# inverter-supply-lv.net
KiCad netlist of a schematic drawn in EAGLE
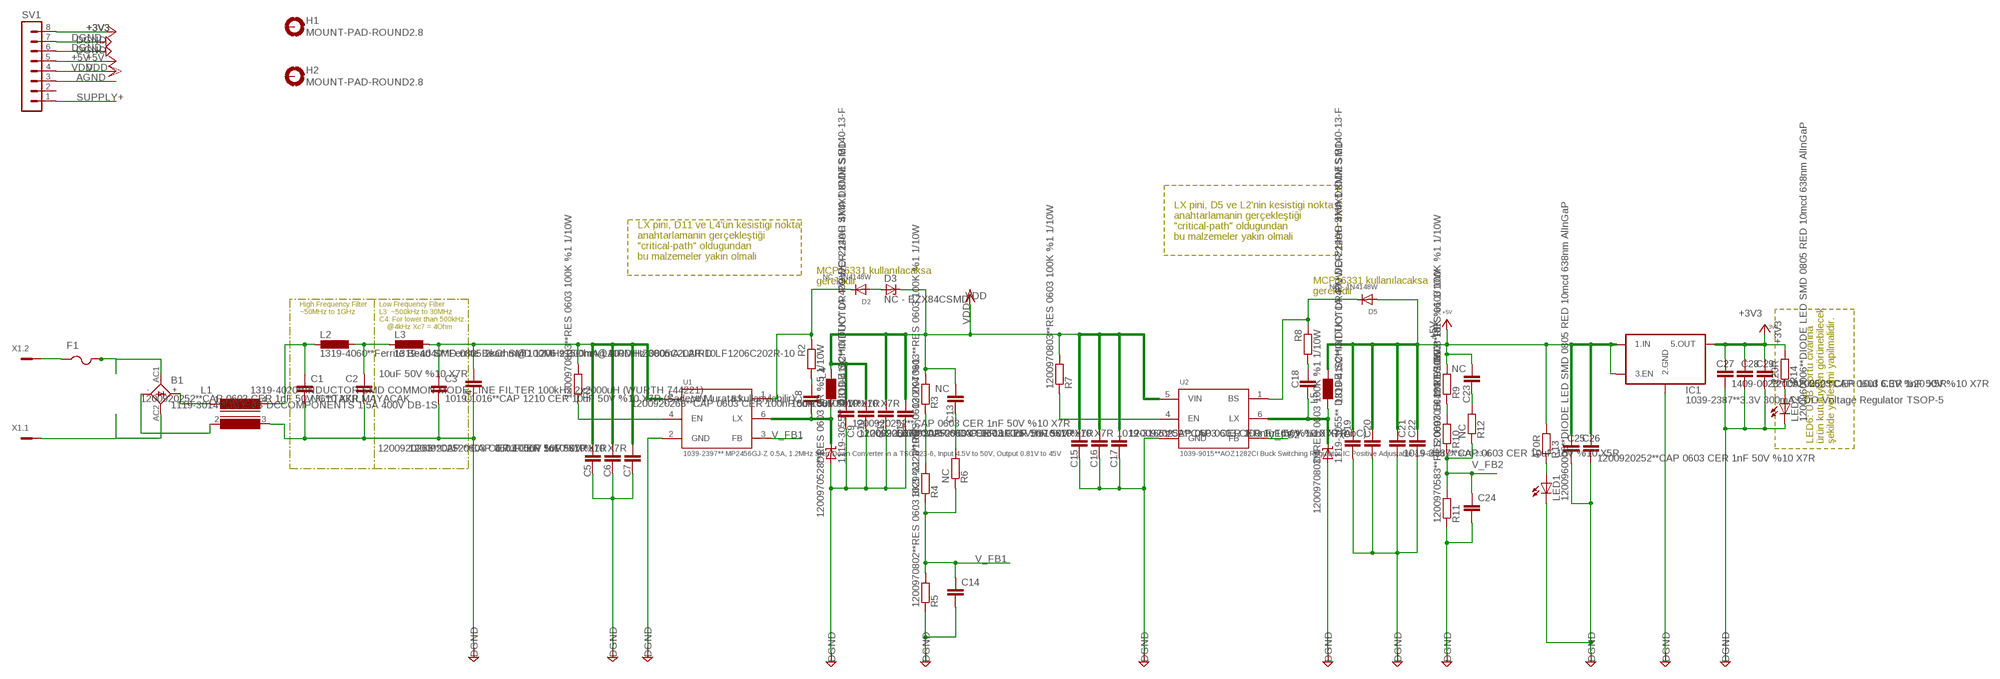
[diagram p0: schematic, sheet 1]

(export (version "E")
  (design (tool "Eeschema 10.0.6"))
  (components
    (comp (ref "B1")
      (value "1119-3014**DB154S DCCOMPONENTS 1.5A 400V DB-1S")
      (footprint "eagle-import:DF005S_DF10S")
      (libsource (lib "eagle-import") (part "DF005S_DF10S"))
    )
    (comp (ref "C1")
      (value "NC**TAKILMAYACAK")
      (footprint "eagle-import:C0603")
      (libsource (lib "eagle-import") (part "C-EUC0603"))
    )
    (comp (ref "C2")
      (value "1200920252**CAP 0603 CER 1nF 50V %10 X7R")
      (footprint "eagle-import:C0603_ENKO")
      (libsource (lib "eagle-import") (part "C-EUC0603E"))
    )
    (comp (ref "C3")
      (value "1019-1016**CAP 1210 CER 10uF 50V %10 X7R (Sadece Murata kullanylabilir)")
      (footprint "eagle-import:C1210")
      (libsource (lib "eagle-import") (part "C-EUC1210"))
    )
    (comp (ref "C4")
      (value "10uF 50V %10 X7R")
      (footprint "eagle-import:C0805_ENKO")
      (libsource (lib "eagle-import") (part "C-EUC0805E"))
    )
    (comp (ref "C5")
      (value "4.7uF 50V %10 X7R")
      (footprint "eagle-import:C0805_ENKO")
      (libsource (lib "eagle-import") (part "C-EUC0805E"))
    )
    (comp (ref "C6")
      (value "1200920268**CAP 0603 CER 100nF 50V %10 X7R")
      (footprint "eagle-import:C0603_ENKO")
      (libsource (lib "eagle-import") (part "C-EUC0603E"))
    )
    (comp (ref "C7")
      (value "1200920252**CAP 0603 CER 1nF 50V %10 X7R")
      (footprint "eagle-import:C0603_ENKO")
      (libsource (lib "eagle-import") (part "C-EUC0603E"))
    )
    (comp (ref "C8")
      (value "1200920268**CAP 0603 CER 100nF 50V %10 X7R")
      (footprint "eagle-import:C0603_ENKO")
      (libsource (lib "eagle-import") (part "C-EUC0603E"))
    )
    (comp (ref "C9")
      (value "1200920252**CAP 0603 CER 1nF 50V %10 X7R")
      (footprint "eagle-import:C0603_ENKO")
      (libsource (lib "eagle-import") (part "C-EUC0603E"))
    )
    (comp (ref "C10")
      (value "1200920268**CAP 0603 CER 100nF 50V %10 X7R")
      (footprint "eagle-import:C0603_ENKO")
      (libsource (lib "eagle-import") (part "C-EUC0603E"))
    )
    (comp (ref "C11")
      (value "10uF 50V %10 X7R")
      (footprint "eagle-import:C0805_ENKO")
      (libsource (lib "eagle-import") (part "C-EUC0805E"))
    )
    (comp (ref "C12")
      (value "10uF 50V %10 X7R")
      (footprint "eagle-import:C0805_ENKO")
      (libsource (lib "eagle-import") (part "C-EUC0805E"))
    )
    (comp (ref "C13")
      (value "NC")
      (footprint "eagle-import:C0603_ENKO")
      (libsource (lib "eagle-import") (part "C-EUC0603E"))
    )
    (comp (ref "C14")
      (value "1200920271**CAP 0603 CER 10pF 50V%10 COG")
      (footprint "eagle-import:C0603_ENKO")
      (libsource (lib "eagle-import") (part "C-EUC0603E"))
    )
    (comp (ref "C15")
      (value "1200920567**CAP 0603 CER 1uF 25V %10X7R")
      (footprint "eagle-import:C0603_ENKO")
      (libsource (lib "eagle-import") (part "C-EUC0603E"))
    )
    (comp (ref "C16")
      (value "1200920268**CAP 0603 CER 100nF 50V %10 X7R")
      (footprint "eagle-import:C0603_ENKO")
      (libsource (lib "eagle-import") (part "C-EUC0603E"))
    )
    (comp (ref "C17")
      (value "1200920252**CAP 0603 CER 1nF 50V %10 X7R")
      (footprint "eagle-import:C0603_ENKO")
      (libsource (lib "eagle-import") (part "C-EUC0603E"))
    )
    (comp (ref "C18")
      (value "1200920268**CAP 0603 CER 100nF 50V %10 X7R")
      (footprint "eagle-import:C0603_ENKO")
      (libsource (lib "eagle-import") (part "C-EUC0603E"))
    )
    (comp (ref "C19")
      (value "1200920252**CAP 0603 CER 1nF 50V %10 X7R")
      (footprint "eagle-import:C0603_ENKO")
      (libsource (lib "eagle-import") (part "C-EUC0603E"))
    )
    (comp (ref "C20")
      (value "1019-3166**CAP 0603 CER 100nF 16V %10 X7R (AbC)")
      (footprint "eagle-import:C0603_ENKO")
      (libsource (lib "eagle-import") (part "C-EUC0603E"))
    )
    (comp (ref "C21")
      (value "1019-3387**CAP 0603 CER 10uF 10V %10 X5R")
      (footprint "eagle-import:C0603_ENKO")
      (libsource (lib "eagle-import") (part "C-EUC0603E"))
    )
    (comp (ref "C22")
      (value "1019-3387**CAP 0603 CER 10uF 10V %10 X5R")
      (footprint "eagle-import:C0603_ENKO")
      (libsource (lib "eagle-import") (part "C-EUC0603E"))
    )
    (comp (ref "C23")
      (value "NC")
      (footprint "eagle-import:C0603_ENKO")
      (libsource (lib "eagle-import") (part "C-EUC0603E"))
    )
    (comp (ref "C24")
      (value "1200920271**CAP 0603 CER 10pF 50V%10 COG")
      (footprint "eagle-import:C0603_ENKO")
      (libsource (lib "eagle-import") (part "C-EUC0603E"))
    )
    (comp (ref "C25")
      (value "1019-3166**CAP 0603 CER 100nF 16V %10 X7R (AbC)")
      (footprint "eagle-import:C0603_ENKO")
      (libsource (lib "eagle-import") (part "C-EUC0603E"))
    )
    (comp (ref "C26")
      (value "1200920252**CAP 0603 CER 1nF 50V %10 X7R")
      (footprint "eagle-import:C0603_ENKO")
      (libsource (lib "eagle-import") (part "C-EUC0603E"))
    )
    (comp (ref "C27")
      (value "1409-0023**CAP 0603 CER 10uf 6.3V %20 X5R")
      (footprint "eagle-import:C0603_ENKO")
      (libsource (lib "eagle-import") (part "C-EUC0603E"))
    )
    (comp (ref "C28")
      (value "1019-3166**CAP 0603 CER 100nF 16V %10 X7R (AbC)")
      (footprint "eagle-import:C0603_ENKO")
      (libsource (lib "eagle-import") (part "C-EUC0603E"))
    )
    (comp (ref "C29")
      (value "1200920252**CAP 0603 CER 1nF 50V %10 X7R")
      (footprint "eagle-import:C0603_ENKO")
      (libsource (lib "eagle-import") (part "C-EUC0603E"))
    )
    (comp (ref "D1")
      (value "1119-3055** DIODE SCHOTTKY 1A 40V DO-214AC SMA DIODES B140-13-F")
      (footprint "eagle-import:SMA")
      (libsource (lib "eagle-import") (part "SD-SMA"))
    )
    (comp (ref "D2")
      (value "NC - 1N4148W")
      (footprint "eagle-import:SOD-123")
      (libsource (lib "eagle-import") (part "DIODESOD-123"))
    )
    (comp (ref "D3")
      (value "NC - BZX84CSMD")
      (footprint "eagle-import:TO236")
      (libsource (lib "eagle-import") (part "BZX84CSMD"))
    )
    (comp (ref "D4")
      (value "1119-3055** DIODE SCHOTTKY 1A 40V DO-214AC SMA DIODES B140-13-F")
      (footprint "eagle-import:SMA")
      (libsource (lib "eagle-import") (part "SD-SMA"))
    )
    (comp (ref "D5")
      (value "NC - 1N4148W")
      (footprint "eagle-import:SOD-123")
      (libsource (lib "eagle-import") (part "DIODESOD-123"))
    )
    (comp (ref "F1")
      (value "PTCFUSE-1206")
      (footprint "eagle-import:R1206")
      (libsource (lib "eagle-import") (part "PTCFUSE-1206"))
    )
    (comp (ref "H1")
      (value "MOUNT-PAD-ROUND2.8")
      (footprint "eagle-import:2,8-PAD")
      (libsource (lib "eagle-import") (part "MOUNT-PAD-ROUND2.8"))
    )
    (comp (ref "H2")
      (value "MOUNT-PAD-ROUND2.8")
      (footprint "eagle-import:2,8-PAD")
      (libsource (lib "eagle-import") (part "MOUNT-PAD-ROUND2.8"))
    )
    (comp (ref "IC1")
      (value "1039-2387**3.3V 300mA LDO Voltage Regulator TSOP-5")
      (footprint "eagle-import:NCP115ASN330T2G")
      (libsource (lib "eagle-import") (part "NCP115ASN330T2G"))
    )
    (comp (ref "L1")
      (value "1319-4020**INDUCTOR SMD COMMON MODE LINE FILTER 100kHz 2x2000uH (WURTH 744221)")
      (footprint "eagle-import:ARYA_COMMON_FILTER")
      (libsource (lib "eagle-import") (part "ARYA_COMMON_FILTER"))
    )
    (comp (ref "L2")
      (value "1319-4060**Ferrite Bead SMD 0805 2kOhm@100MHz 300mA LAIRD HZ0805C202R-10")
      (footprint "eagle-import:L2012C")
      (libsource (lib "eagle-import") (part "L-EUL2012C"))
    )
    (comp (ref "L3")
      (value "1319-4040**Ferrite Bead SMD 1206 915Ohm@100MHz 300mA LAIRD LF1206C202R-10")
      (footprint "eagle-import:L3216C")
      (libsource (lib "eagle-import") (part "L-EUL3216C"))
    )
    (comp (ref "L4")
      (value "1319-4102**INDUCTOR POWER 22UH 4X4X1.8MM SMD")
      (footprint "eagle-import:WE-PD2_S")
      (libsource (lib "eagle-import") (part "WE-PD2_S"))
    )
    (comp (ref "L5")
      (value "1319-4102**INDUCTOR POWER 22UH 4X4X1.8MM SMD")
      (footprint "eagle-import:WE-PD2_S")
      (libsource (lib "eagle-import") (part "WE-PD2_S"))
    )
    (comp (ref "LED1")
      (value "1200960006**DIODE LED SMD 0805 RED 10mcd 638nm AlInGaP")
      (footprint "eagle-import:CHIP-LED0805")
      (libsource (lib "eagle-import") (part "LEDCHIP-LED0805"))
    )
    (comp (ref "LED2")
      (value "1200960006**DIODE LED SMD 0805 RED 10mcd 638nm AlInGaP")
      (footprint "eagle-import:CHIP-LED0805")
      (libsource (lib "eagle-import") (part "LEDCHIP-LED0805"))
    )
    (comp (ref "R1")
      (value "1200970803**RES 0603 100K %1 1/10W")
      (footprint "eagle-import:R0603_ENKO")
      (libsource (lib "eagle-import") (part "R-EU_R0603E"))
    )
    (comp (ref "R2")
      (value "1200970528**RES 0603 0R %5 1/10W")
      (footprint "eagle-import:R0603_ENKO")
      (libsource (lib "eagle-import") (part "R-EU_R0603E"))
    )
    (comp (ref "R3")
      (value "1200970803**RES 0603 100K %1 1/10W")
      (footprint "eagle-import:R0603_ENKO")
      (libsource (lib "eagle-import") (part "R-EU_R0603E"))
    )
    (comp (ref "R4")
      (value "1029-2223**RES 0603 2K4 %1")
      (footprint "eagle-import:R0603_ENKO")
      (libsource (lib "eagle-import") (part "R-EU_R0603E"))
    )
    (comp (ref "R5")
      (value "1200970802**RES 0603 3K3 %1 1/10W")
      (footprint "eagle-import:R0603_ENKO")
      (libsource (lib "eagle-import") (part "R-EU_R0603E"))
    )
    (comp (ref "R6")
      (value "NC")
      (footprint "eagle-import:R0603_ENKO")
      (libsource (lib "eagle-import") (part "R-EU_R0603E"))
    )
    (comp (ref "R7")
      (value "1200970803**RES 0603 100K %1 1/10W")
      (footprint "eagle-import:R0603_ENKO")
      (libsource (lib "eagle-import") (part "R-EU_R0603E"))
    )
    (comp (ref "R8")
      (value "1200970803**RES 0603 100K %1 1/10W")
      (footprint "eagle-import:R0603_ENKO")
      (libsource (lib "eagle-import") (part "R-EU_R0603E"))
    )
    (comp (ref "R9")
      (value "1200970803**RES 0603 100K %1 1/10W")
      (footprint "eagle-import:R0603_ENKO")
      (libsource (lib "eagle-import") (part "R-EU_R0603E"))
    )
    (comp (ref "R10")
      (value "1200970584**RES 0603 18K %1 1/10W")
      (footprint "eagle-import:R0603_ENKO")
      (libsource (lib "eagle-import") (part "R-EU_R0603E"))
    )
    (comp (ref "R11")
      (value "1200970583**RES 0603 1K %1 1/10W")
      (footprint "eagle-import:R0603_ENKO")
      (libsource (lib "eagle-import") (part "R-EU_R0603E"))
    )
    (comp (ref "R12")
      (value "NC")
      (footprint "eagle-import:R0603_ENKO")
      (libsource (lib "eagle-import") (part "R-EU_R0603E"))
    )
    (comp (ref "R13")
      (value "470R")
      (footprint "eagle-import:R0603_ENKO")
      (libsource (lib "eagle-import") (part "R-EU_R0603E"))
    )
    (comp (ref "R14")
      (value "220R")
      (footprint "eagle-import:R0603_ENKO")
      (libsource (lib "eagle-import") (part "R-EU_R0603E"))
    )
    (comp (ref "SV1")
      (value "MA08-1")
      (footprint "eagle-import:MA08-1")
      (libsource (lib "eagle-import") (part "MA08-1"))
    )
    (comp (ref "U1")
      (value "1039-2397** MP2456GJ-Z 0.5A, 1.2MHz Step-Down Converter in a TSOT23-6, Input 4.5V to 50V, Output 0.81V to 45V")
      (footprint "eagle-import:AOZ1282CI-1")
      (libsource (lib "eagle-import") (part "AOZ1282CI-1"))
    )
    (comp (ref "U2")
      (value "1039-9015**AOZ1282CI Buck Switching Regulator IC Positive Adjustable 4.5-36V 1.2A SOT-23-6")
      (footprint "eagle-import:AOZ1282CI-1")
      (libsource (lib "eagle-import") (part "AOZ1282CI-1"))
    )
    (comp (ref "X1")
      (value "0289-9066**15EDGVC-3.81-02P-14")
      (footprint "eagle-import:MCV2")
      (libsource (lib "eagle-import") (part "MCV2"))
    )
  )
  (nets
    (net (code "1") (name "+3V3") (class "Default")
      (node (ref "C27") (pin "1") (pinfunction "1_1") (pintype "passive"))
      (node (ref "C28") (pin "1") (pinfunction "1_1") (pintype "passive"))
      (node (ref "C29") (pin "1") (pinfunction "1_1") (pintype "passive"))
      (node (ref "IC1") (pin "5") (pinfunction "5.OUT_5") (pintype "passive"))
      (node (ref "R14") (pin "2") (pinfunction "2_2") (pintype "passive"))
      (node (ref "SV1") (pin "8") (pinfunction "8_8") (pintype "passive"))
    )
    (net (code "2") (name "+5V") (class "Default")
      (node (ref "C19") (pin "2") (pinfunction "2_2") (pintype "passive"))
      (node (ref "C20") (pin "2") (pinfunction "2_2") (pintype "passive"))
      (node (ref "C21") (pin "1") (pinfunction "1_1") (pintype "passive"))
      (node (ref "C22") (pin "1") (pinfunction "1_1") (pintype "passive"))
      (node (ref "C23") (pin "2") (pinfunction "2_2") (pintype "passive"))
      (node (ref "C25") (pin "1") (pinfunction "1_1") (pintype "passive"))
      (node (ref "C26") (pin "1") (pinfunction "1_1") (pintype "passive"))
      (node (ref "D5") (pin "A") (pinfunction "A_A") (pintype "passive"))
      (node (ref "IC1") (pin "1") (pinfunction "1.IN_1") (pintype "input"))
      (node (ref "IC1") (pin "3") (pinfunction "3.EN_3") (pintype "input"))
      (node (ref "L5") (pin "1") (pinfunction "2_1") (pintype "passive"))
      (node (ref "R13") (pin "2") (pinfunction "2_2") (pintype "passive"))
      (node (ref "R9") (pin "2") (pinfunction "2_2") (pintype "passive"))
      (node (ref "SV1") (pin "5") (pinfunction "5_5") (pintype "passive"))
    )
    (net (code "3") (name "/AGND") (class "Default")
      (node (ref "SV1") (pin "3") (pinfunction "3_3") (pintype "passive"))
    )
    (net (code "4") (name "/SUPPLY+") (class "Default")
      (node (ref "SV1") (pin "1") (pinfunction "1_1") (pintype "passive"))
    )
    (net (code "5") (name "/V_FB1") (class "Default")
      (node (ref "C14") (pin "1") (pinfunction "1_1") (pintype "passive"))
      (node (ref "R4") (pin "1") (pinfunction "1_1") (pintype "passive"))
      (node (ref "R5") (pin "2") (pinfunction "2_2") (pintype "passive"))
      (node (ref "R6") (pin "1") (pinfunction "1_1") (pintype "passive"))
      (node (ref "U1") (pin "3") (pinfunction "FB_3") (pintype "bidirectional"))
    )
    (net (code "6") (name "/V_FB2") (class "Default")
      (node (ref "C24") (pin "1") (pinfunction "1_1") (pintype "passive"))
      (node (ref "R10") (pin "1") (pinfunction "1_1") (pintype "passive"))
      (node (ref "R11") (pin "2") (pinfunction "2_2") (pintype "passive"))
      (node (ref "R12") (pin "1") (pinfunction "1_1") (pintype "passive"))
      (node (ref "U2") (pin "3") (pinfunction "FB_3") (pintype "bidirectional"))
    )
    (net (code "7") (name "DGND") (class "Default")
      (node (ref "C1") (pin "1") (pinfunction "1_1") (pintype "passive"))
      (node (ref "C10") (pin "1") (pinfunction "1_1") (pintype "passive"))
      (node (ref "C11") (pin "1") (pinfunction "1_1") (pintype "passive"))
      (node (ref "C12") (pin "1") (pinfunction "1_1") (pintype "passive"))
      (node (ref "C14") (pin "2") (pinfunction "2_2") (pintype "passive"))
      (node (ref "C15") (pin "1") (pinfunction "1_1") (pintype "passive"))
      (node (ref "C16") (pin "1") (pinfunction "1_1") (pintype "passive"))
      (node (ref "C17") (pin "1") (pinfunction "1_1") (pintype "passive"))
      (node (ref "C19") (pin "1") (pinfunction "1_1") (pintype "passive"))
      (node (ref "C2") (pin "2") (pinfunction "2_2") (pintype "passive"))
      (node (ref "C20") (pin "1") (pinfunction "1_1") (pintype "passive"))
      (node (ref "C21") (pin "2") (pinfunction "2_2") (pintype "passive"))
      (node (ref "C22") (pin "2") (pinfunction "2_2") (pintype "passive"))
      (node (ref "C24") (pin "2") (pinfunction "2_2") (pintype "passive"))
      (node (ref "C25") (pin "2") (pinfunction "2_2") (pintype "passive"))
      (node (ref "C26") (pin "2") (pinfunction "2_2") (pintype "passive"))
      (node (ref "C27") (pin "2") (pinfunction "2_2") (pintype "passive"))
      (node (ref "C28") (pin "2") (pinfunction "2_2") (pintype "passive"))
      (node (ref "C29") (pin "2") (pinfunction "2_2") (pintype "passive"))
      (node (ref "C3") (pin "1") (pinfunction "1_1") (pintype "passive"))
      (node (ref "C4") (pin "1") (pinfunction "1_1") (pintype "passive"))
      (node (ref "C5") (pin "1") (pinfunction "1_1") (pintype "passive"))
      (node (ref "C6") (pin "1") (pinfunction "1_1") (pintype "passive"))
      (node (ref "C7") (pin "1") (pinfunction "1_1") (pintype "passive"))
      (node (ref "C9") (pin "2") (pinfunction "2_2") (pintype "passive"))
      (node (ref "D1") (pin "A") (pinfunction "A_A") (pintype "passive"))
      (node (ref "D4") (pin "A") (pinfunction "A_A") (pintype "passive"))
      (node (ref "IC1") (pin "2") (pinfunction "2.GND_2") (pintype "input"))
      (node (ref "L1") (pin "3") (pinfunction "3_3") (pintype "passive"))
      (node (ref "LED1") (pin "C") (pinfunction "C_C") (pintype "passive"))
      (node (ref "LED2") (pin "C") (pinfunction "C_C") (pintype "passive"))
      (node (ref "R11") (pin "1") (pinfunction "1_1") (pintype "passive"))
      (node (ref "R5") (pin "1") (pinfunction "1_1") (pintype "passive"))
      (node (ref "SV1") (pin "6") (pinfunction "6_6") (pintype "passive"))
      (node (ref "SV1") (pin "7") (pinfunction "7_7") (pintype "passive"))
      (node (ref "U1") (pin "2") (pinfunction "GND_2") (pintype "bidirectional"))
      (node (ref "U2") (pin "2") (pinfunction "GND_2") (pintype "bidirectional"))
    )
    (net (code "8") (name "Net-(B1-Pad+)") (class "Default")
      (node (ref "B1") (pin "+") (pinfunction "+_+") (pintype "passive"))
      (node (ref "L1") (pin "1") (pinfunction "1_1") (pintype "passive"))
    )
    (net (code "9") (name "Net-(B1-Pad-)") (class "Default")
      (node (ref "B1") (pin "-") (pinfunction "-_-") (pintype "passive"))
      (node (ref "L1") (pin "2") (pinfunction "2_2") (pintype "passive"))
    )
    (net (code "10") (name "Net-(B1-PadAC1)") (class "Default")
      (node (ref "B1") (pin "AC1") (pinfunction "AC1_AC1") (pintype "passive"))
      (node (ref "F1") (pin "2") (pinfunction "2_2") (pintype "passive"))
    )
    (net (code "11") (name "Net-(C1-Pad2)") (class "Default")
      (node (ref "C1") (pin "2") (pinfunction "2_2") (pintype "passive"))
      (node (ref "L1") (pin "4") (pinfunction "4_4") (pintype "passive"))
      (node (ref "L2") (pin "1") (pinfunction "1_1") (pintype "passive"))
    )
    (net (code "12") (name "Net-(C2-Pad1)") (class "Default")
      (node (ref "C2") (pin "1") (pinfunction "1_1") (pintype "passive"))
      (node (ref "L2") (pin "2") (pinfunction "2_2") (pintype "passive"))
      (node (ref "L3") (pin "1") (pinfunction "1_1") (pintype "passive"))
    )
    (net (code "13") (name "Net-(C8-Pad1)") (class "Default")
      (node (ref "C8") (pin "1") (pinfunction "1_1") (pintype "passive"))
      (node (ref "R2") (pin "2") (pinfunction "2_2") (pintype "passive"))
    )
    (net (code "14") (name "Net-(C13-Pad1)") (class "Default")
      (node (ref "C13") (pin "1") (pinfunction "1_1") (pintype "passive"))
      (node (ref "R6") (pin "2") (pinfunction "2_2") (pintype "passive"))
    )
    (net (code "15") (name "Net-(C18-Pad1)") (class "Default")
      (node (ref "C18") (pin "1") (pinfunction "1_1") (pintype "passive"))
      (node (ref "R8") (pin "2") (pinfunction "2_2") (pintype "passive"))
    )
    (net (code "16") (name "Net-(C23-Pad1)") (class "Default")
      (node (ref "C23") (pin "1") (pinfunction "1_1") (pintype "passive"))
      (node (ref "R12") (pin "2") (pinfunction "2_2") (pintype "passive"))
    )
    (net (code "17") (name "Net-(D2-PadA)") (class "Default")
      (node (ref "D2") (pin "A") (pinfunction "A_A") (pintype "passive"))
      (node (ref "D3") (pin "A") (pinfunction "A_A") (pintype "passive"))
    )
    (net (code "18") (name "Net-(L4-1)") (class "Default")
      (node (ref "C8") (pin "2") (pinfunction "2_2") (pintype "passive"))
      (node (ref "D1") (pin "C") (pinfunction "C_C") (pintype "passive"))
      (node (ref "L4") (pin "2") (pinfunction "1_2") (pintype "passive"))
      (node (ref "U1") (pin "6") (pinfunction "LX_6") (pintype "bidirectional"))
    )
    (net (code "19") (name "Net-(L5-1)") (class "Default")
      (node (ref "C18") (pin "2") (pinfunction "2_2") (pintype "passive"))
      (node (ref "D4") (pin "C") (pinfunction "C_C") (pintype "passive"))
      (node (ref "L5") (pin "2") (pinfunction "1_2") (pintype "passive"))
      (node (ref "U2") (pin "6") (pinfunction "LX_6") (pintype "bidirectional"))
    )
    (net (code "20") (name "Net-(LED1-PadA)") (class "Default")
      (node (ref "LED1") (pin "A") (pinfunction "A_A") (pintype "passive"))
      (node (ref "R13") (pin "1") (pinfunction "1_1") (pintype "passive"))
    )
    (net (code "21") (name "Net-(LED2-PadA)") (class "Default")
      (node (ref "LED2") (pin "A") (pinfunction "A_A") (pintype "passive"))
      (node (ref "R14") (pin "1") (pinfunction "1_1") (pintype "passive"))
    )
    (net (code "22") (name "Net-(R3-Pad1)") (class "Default")
      (node (ref "R3") (pin "1") (pinfunction "1_1") (pintype "passive"))
      (node (ref "R4") (pin "2") (pinfunction "2_2") (pintype "passive"))
    )
    (net (code "23") (name "Net-(R10-Pad2)") (class "Default")
      (node (ref "R10") (pin "2") (pinfunction "2_2") (pintype "passive"))
      (node (ref "R9") (pin "1") (pinfunction "1_1") (pintype "passive"))
    )
    (net (code "24") (name "Net-(U1-BS)") (class "Default")
      (node (ref "D2") (pin "C") (pinfunction "C_C") (pintype "passive"))
      (node (ref "R2") (pin "1") (pinfunction "1_1") (pintype "passive"))
      (node (ref "U1") (pin "1") (pinfunction "BS_1") (pintype "bidirectional"))
    )
    (net (code "25") (name "Net-(U1-EN)") (class "Default")
      (node (ref "R1") (pin "1") (pinfunction "1_1") (pintype "passive"))
      (node (ref "U1") (pin "4") (pinfunction "EN_4") (pintype "bidirectional"))
    )
    (net (code "26") (name "Net-(U1-VIN)") (class "Default")
      (node (ref "C3") (pin "2") (pinfunction "2_2") (pintype "passive"))
      (node (ref "C4") (pin "2") (pinfunction "2_2") (pintype "passive"))
      (node (ref "C5") (pin "2") (pinfunction "2_2") (pintype "passive"))
      (node (ref "C6") (pin "2") (pinfunction "2_2") (pintype "passive"))
      (node (ref "C7") (pin "2") (pinfunction "2_2") (pintype "passive"))
      (node (ref "L3") (pin "2") (pinfunction "2_2") (pintype "passive"))
      (node (ref "R1") (pin "2") (pinfunction "2_2") (pintype "passive"))
      (node (ref "U1") (pin "5") (pinfunction "VIN_5") (pintype "bidirectional"))
    )
    (net (code "27") (name "Net-(U2-BS)") (class "Default")
      (node (ref "D5") (pin "C") (pinfunction "C_C") (pintype "passive"))
      (node (ref "R8") (pin "1") (pinfunction "1_1") (pintype "passive"))
      (node (ref "U2") (pin "1") (pinfunction "BS_1") (pintype "bidirectional"))
    )
    (net (code "28") (name "Net-(U2-EN)") (class "Default")
      (node (ref "R7") (pin "1") (pinfunction "1_1") (pintype "passive"))
      (node (ref "U2") (pin "4") (pinfunction "EN_4") (pintype "bidirectional"))
    )
    (net (code "29") (name "Net-(X1A-SK)") (class "Default")
      (node (ref "B1") (pin "AC2") (pinfunction "AC2_AC2") (pintype "passive"))
      (node (ref "X1") (pin "1") (pinfunction "SK_1") (pintype "passive"))
    )
    (net (code "30") (name "Net-(X1B-SK)") (class "Default")
      (node (ref "F1") (pin "1") (pinfunction "1_1") (pintype "passive"))
      (node (ref "X1") (pin "2") (pinfunction "SK_2") (pintype "passive"))
    )
    (net (code "31") (name "VDD") (class "Default")
      (node (ref "C10") (pin "2") (pinfunction "2_2") (pintype "passive"))
      (node (ref "C11") (pin "2") (pinfunction "2_2") (pintype "passive"))
      (node (ref "C12") (pin "2") (pinfunction "2_2") (pintype "passive"))
      (node (ref "C13") (pin "2") (pinfunction "2_2") (pintype "passive"))
      (node (ref "C15") (pin "2") (pinfunction "2_2") (pintype "passive"))
      (node (ref "C16") (pin "2") (pinfunction "2_2") (pintype "passive"))
      (node (ref "C17") (pin "2") (pinfunction "2_2") (pintype "passive"))
      (node (ref "C9") (pin "1") (pinfunction "1_1") (pintype "passive"))
      (node (ref "D3") (pin "C") (pinfunction "C_C") (pintype "passive"))
      (node (ref "L4") (pin "1") (pinfunction "2_1") (pintype "passive"))
      (node (ref "R3") (pin "2") (pinfunction "2_2") (pintype "passive"))
      (node (ref "R7") (pin "2") (pinfunction "2_2") (pintype "passive"))
      (node (ref "SV1") (pin "4") (pinfunction "4_4") (pintype "passive"))
      (node (ref "U2") (pin "5") (pinfunction "VIN_5") (pintype "bidirectional"))
    )
    (net (code "32") (name "unconnected-(H1-MOUNT-PadB2,8)") (class "Default")
      (node (ref "H1") (pin "B2,8") (pinfunction "MOUNT_B2,8") (pintype "passive"))
    )
    (net (code "33") (name "unconnected-(H2-MOUNT-PadB2,8)") (class "Default")
      (node (ref "H2") (pin "B2,8") (pinfunction "MOUNT_B2,8") (pintype "passive"))
    )
    (net (code "34") (name "unconnected-(SV1-Pad2)") (class "Default")
      (node (ref "SV1") (pin "2") (pinfunction "2_2") (pintype "passive"))
    )
  )
)
